# lorelei_A_v1.net
KiCad netlist of a schematic drawn in EAGLE
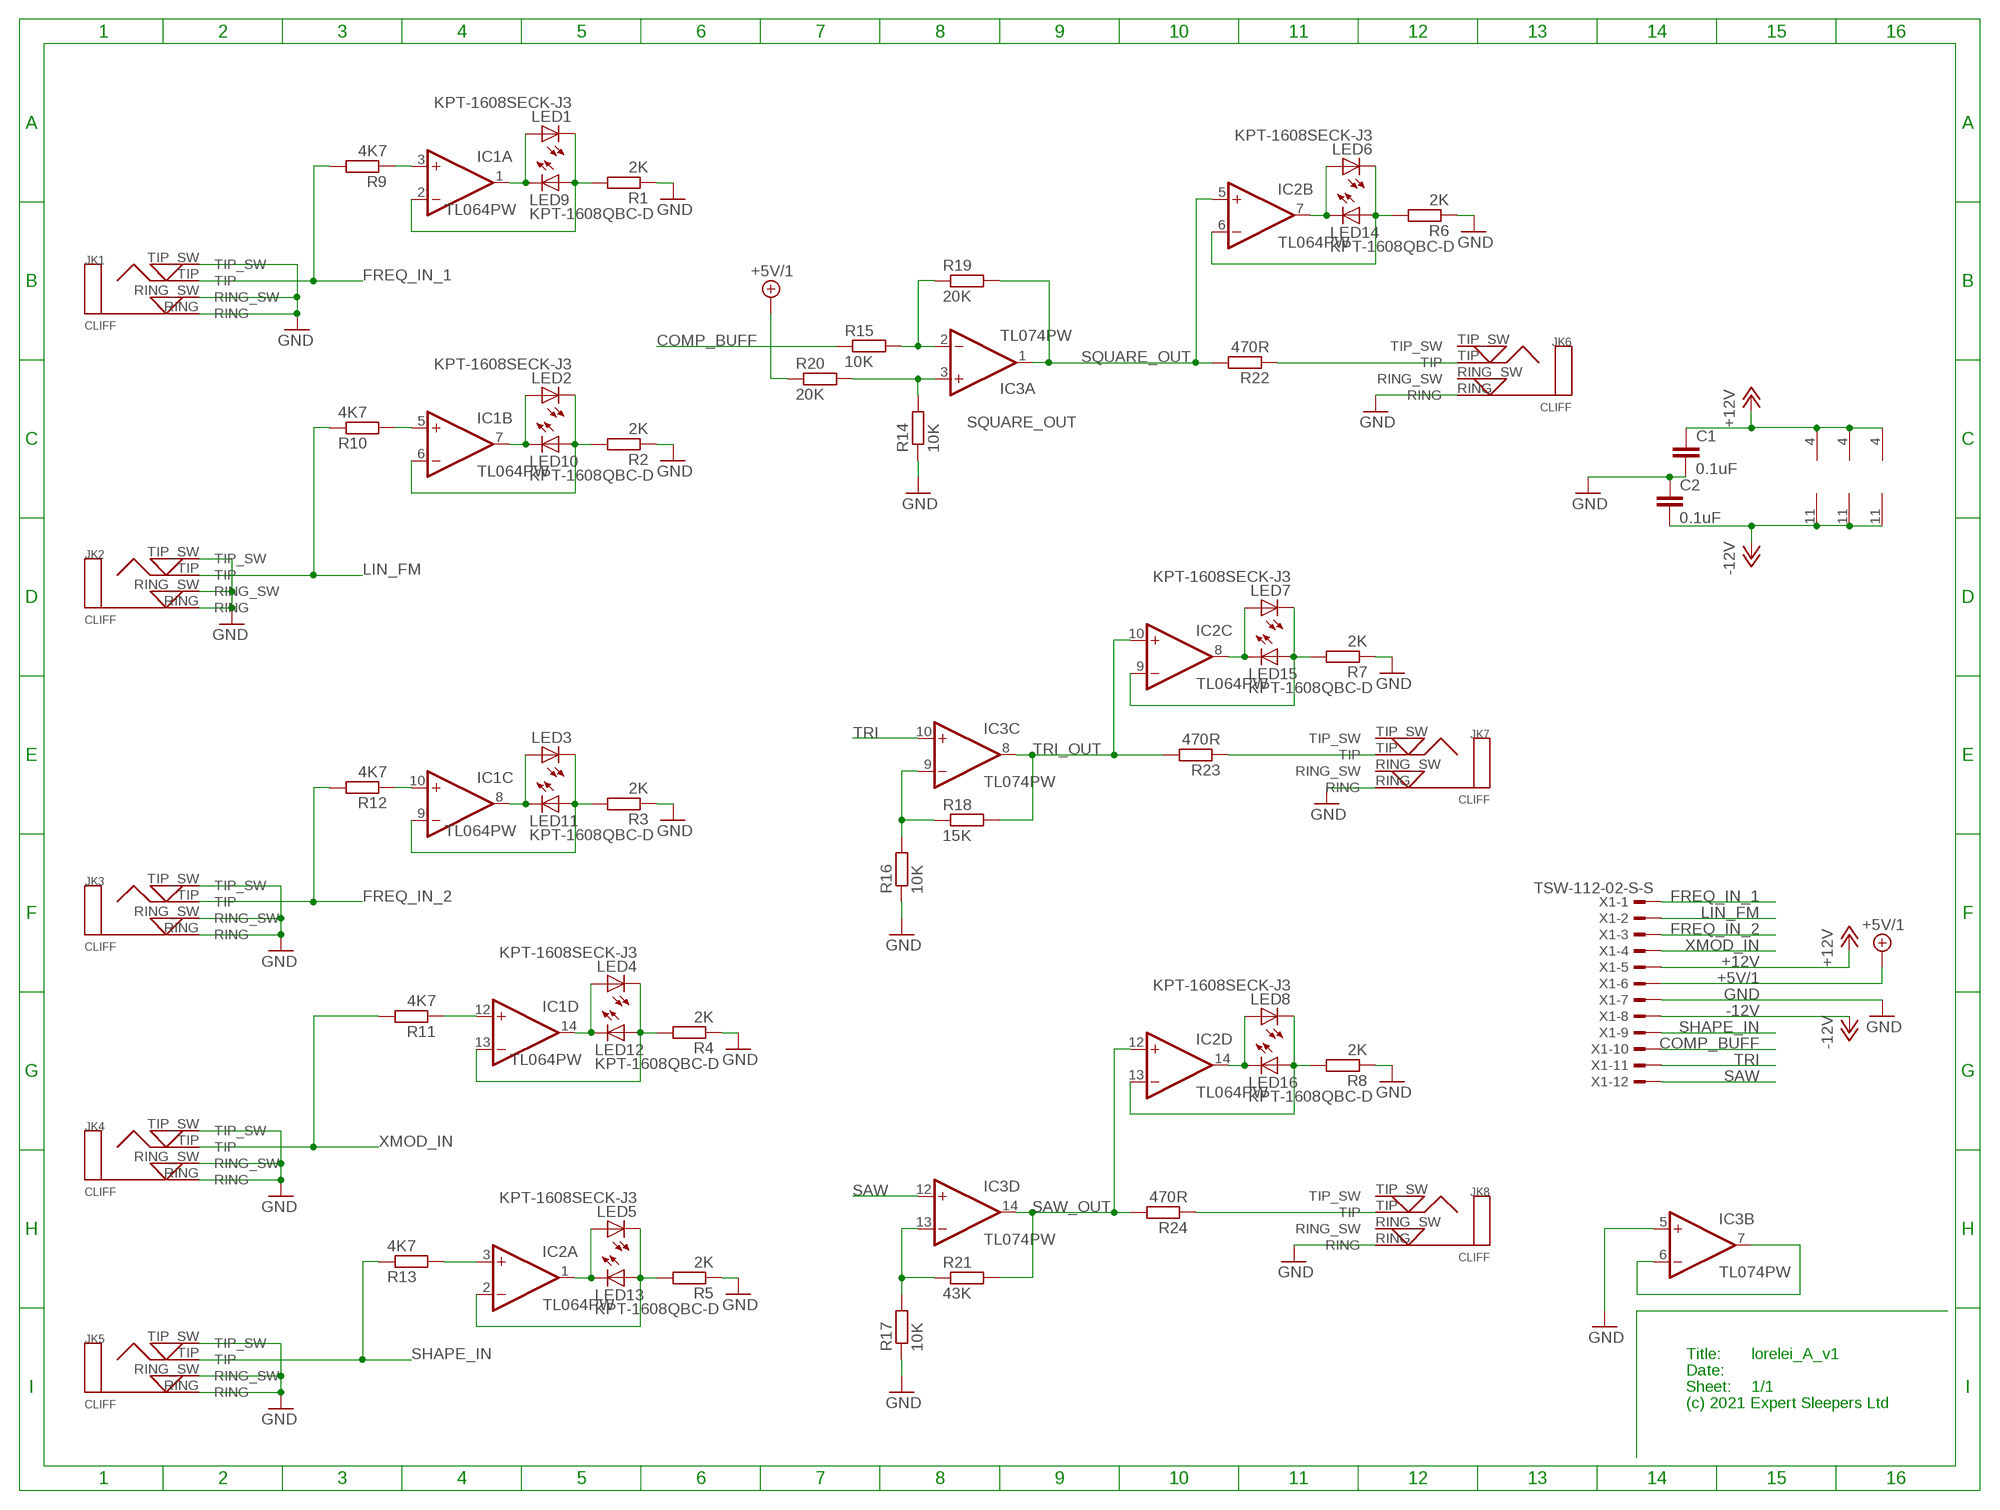
[diagram p0: schematic, sheet 1]

(export (version "E")
  (design (tool "Eeschema 10.0.6"))
  (components
    (comp (ref "C1")
      (value "0.1uF")
      (footprint "eagle-import:C0402")
      (libsource (lib "eagle-import") (part "C-EUC0402"))
    )
    (comp (ref "C2")
      (value "0.1uF")
      (footprint "eagle-import:C0402")
      (libsource (lib "eagle-import") (part "C-EUC0402"))
    )
    (comp (ref "IC1")
      (value "TL064PW")
      (footprint "eagle-import:PW_R-PDSO-G14")
      (libsource (lib "eagle-import") (part "TL074PW"))
    )
    (comp (ref "IC2")
      (value "TL064PW")
      (footprint "eagle-import:PW_R-PDSO-G14")
      (libsource (lib "eagle-import") (part "TL074PW"))
    )
    (comp (ref "IC3")
      (value "TL074PW")
      (footprint "eagle-import:PW_R-PDSO-G14")
      (libsource (lib "eagle-import") (part "TL074PW"))
    )
    (comp (ref "JK1")
      (value "CLIFF")
      (footprint "eagle-import:CLIFF3.5MMPCB")
      (libsource (lib "eagle-import") (part "CLIFF3.5MM_PCB_SW_JK"))
    )
    (comp (ref "JK2")
      (value "CLIFF")
      (footprint "eagle-import:CLIFF3.5MMPCB")
      (libsource (lib "eagle-import") (part "CLIFF3.5MM_PCB_SW_JK"))
    )
    (comp (ref "JK3")
      (value "CLIFF")
      (footprint "eagle-import:CLIFF3.5MMPCB")
      (libsource (lib "eagle-import") (part "CLIFF3.5MM_PCB_SW_JK"))
    )
    (comp (ref "JK4")
      (value "CLIFF")
      (footprint "eagle-import:CLIFF3.5MMPCB")
      (libsource (lib "eagle-import") (part "CLIFF3.5MM_PCB_SW_JK"))
    )
    (comp (ref "JK5")
      (value "CLIFF")
      (footprint "eagle-import:CLIFF3.5MMPCB")
      (libsource (lib "eagle-import") (part "CLIFF3.5MM_PCB_SW_JK"))
    )
    (comp (ref "JK6")
      (value "CLIFF")
      (footprint "eagle-import:CLIFF3.5MMPCB")
      (libsource (lib "eagle-import") (part "CLIFF3.5MM_PCB_SW_JK"))
    )
    (comp (ref "JK7")
      (value "CLIFF")
      (footprint "eagle-import:CLIFF3.5MMPCB")
      (libsource (lib "eagle-import") (part "CLIFF3.5MM_PCB_SW_JK"))
    )
    (comp (ref "JK8")
      (value "CLIFF")
      (footprint "eagle-import:CLIFF3.5MMPCB")
      (libsource (lib "eagle-import") (part "CLIFF3.5MM_PCB_SW_JK"))
    )
    (comp (ref "LED1")
      (value "KPT-1608SECK-J3")
      (footprint "eagle-import:CHIPLED_0603_LEFT")
      (libsource (lib "eagle-import") (part "KPT-1608SECK-J3"))
    )
    (comp (ref "LED2")
      (value "KPT-1608SECK-J3")
      (footprint "eagle-import:CHIPLED_0603_LEFT")
      (libsource (lib "eagle-import") (part "KPT-1608SECK-J3"))
    )
    (comp (ref "LED3")
      (value "KPT-1608SECK-J3")
      (footprint "eagle-import:CHIPLED_0603_LEFT")
      (libsource (lib "eagle-import") (part "KPT-1608SECK-J3"))
    )
    (comp (ref "LED4")
      (value "KPT-1608SECK-J3")
      (footprint "eagle-import:CHIPLED_0603_LEFT")
      (libsource (lib "eagle-import") (part "KPT-1608SECK-J3"))
    )
    (comp (ref "LED5")
      (value "KPT-1608SECK-J3")
      (footprint "eagle-import:CHIPLED_0603_LEFT")
      (libsource (lib "eagle-import") (part "KPT-1608SECK-J3"))
    )
    (comp (ref "LED6")
      (value "KPT-1608SECK-J3")
      (footprint "eagle-import:CHIPLED_0603_LEFT")
      (libsource (lib "eagle-import") (part "KPT-1608SECK-J3"))
    )
    (comp (ref "LED7")
      (value "KPT-1608SECK-J3")
      (footprint "eagle-import:CHIPLED_0603_LEFT")
      (libsource (lib "eagle-import") (part "KPT-1608SECK-J3"))
    )
    (comp (ref "LED8")
      (value "KPT-1608SECK-J3")
      (footprint "eagle-import:CHIPLED_0603_LEFT")
      (libsource (lib "eagle-import") (part "KPT-1608SECK-J3"))
    )
    (comp (ref "LED9")
      (value "KPT-1608QBC-D")
      (footprint "eagle-import:CHIPLED_0603_RIGHT")
      (libsource (lib "eagle-import") (part "KPT-1608QBC-D"))
    )
    (comp (ref "LED10")
      (value "KPT-1608QBC-D")
      (footprint "eagle-import:CHIPLED_0603_RIGHT")
      (libsource (lib "eagle-import") (part "KPT-1608QBC-D"))
    )
    (comp (ref "LED11")
      (value "KPT-1608QBC-D")
      (footprint "eagle-import:CHIPLED_0603_RIGHT")
      (libsource (lib "eagle-import") (part "KPT-1608QBC-D"))
    )
    (comp (ref "LED12")
      (value "KPT-1608QBC-D")
      (footprint "eagle-import:CHIPLED_0603_RIGHT")
      (libsource (lib "eagle-import") (part "KPT-1608QBC-D"))
    )
    (comp (ref "LED13")
      (value "KPT-1608QBC-D")
      (footprint "eagle-import:CHIPLED_0603_RIGHT")
      (libsource (lib "eagle-import") (part "KPT-1608QBC-D"))
    )
    (comp (ref "LED14")
      (value "KPT-1608QBC-D")
      (footprint "eagle-import:CHIPLED_0603_RIGHT")
      (libsource (lib "eagle-import") (part "KPT-1608QBC-D"))
    )
    (comp (ref "LED15")
      (value "KPT-1608QBC-D")
      (footprint "eagle-import:CHIPLED_0603_RIGHT")
      (libsource (lib "eagle-import") (part "KPT-1608QBC-D"))
    )
    (comp (ref "LED16")
      (value "KPT-1608QBC-D")
      (footprint "eagle-import:CHIPLED_0603_RIGHT")
      (libsource (lib "eagle-import") (part "KPT-1608QBC-D"))
    )
    (comp (ref "R1")
      (value "2K")
      (footprint "eagle-import:R1206")
      (libsource (lib "eagle-import") (part "R-EU_R1206"))
    )
    (comp (ref "R2")
      (value "2K")
      (footprint "eagle-import:R1206")
      (libsource (lib "eagle-import") (part "R-EU_R1206"))
    )
    (comp (ref "R3")
      (value "2K")
      (footprint "eagle-import:R1206")
      (libsource (lib "eagle-import") (part "R-EU_R1206"))
    )
    (comp (ref "R4")
      (value "2K")
      (footprint "eagle-import:R1206")
      (libsource (lib "eagle-import") (part "R-EU_R1206"))
    )
    (comp (ref "R5")
      (value "2K")
      (footprint "eagle-import:R1206")
      (libsource (lib "eagle-import") (part "R-EU_R1206"))
    )
    (comp (ref "R6")
      (value "2K")
      (footprint "eagle-import:R1206")
      (libsource (lib "eagle-import") (part "R-EU_R1206"))
    )
    (comp (ref "R7")
      (value "2K")
      (footprint "eagle-import:R1206")
      (libsource (lib "eagle-import") (part "R-EU_R1206"))
    )
    (comp (ref "R8")
      (value "2K")
      (footprint "eagle-import:R1206")
      (libsource (lib "eagle-import") (part "R-EU_R1206"))
    )
    (comp (ref "R9")
      (value "4K7")
      (footprint "eagle-import:R1206")
      (libsource (lib "eagle-import") (part "R-EU_R1206"))
    )
    (comp (ref "R10")
      (value "4K7")
      (footprint "eagle-import:R1206")
      (libsource (lib "eagle-import") (part "R-EU_R1206"))
    )
    (comp (ref "R11")
      (value "4K7")
      (footprint "eagle-import:R1206")
      (libsource (lib "eagle-import") (part "R-EU_R1206"))
    )
    (comp (ref "R12")
      (value "4K7")
      (footprint "eagle-import:R1206")
      (libsource (lib "eagle-import") (part "R-EU_R1206"))
    )
    (comp (ref "R13")
      (value "4K7")
      (footprint "eagle-import:R1206")
      (libsource (lib "eagle-import") (part "R-EU_R1206"))
    )
    (comp (ref "R14")
      (value "10K")
      (footprint "eagle-import:R0603")
      (libsource (lib "eagle-import") (part "R-EU_R0603"))
    )
    (comp (ref "R15")
      (value "10K")
      (footprint "eagle-import:R0603")
      (libsource (lib "eagle-import") (part "R-EU_R0603"))
    )
    (comp (ref "R16")
      (value "10K")
      (footprint "eagle-import:R0603")
      (libsource (lib "eagle-import") (part "R-EU_R0603"))
    )
    (comp (ref "R17")
      (value "10K")
      (footprint "eagle-import:R0603")
      (libsource (lib "eagle-import") (part "R-EU_R0603"))
    )
    (comp (ref "R18")
      (value "15K")
      (footprint "eagle-import:R0603")
      (libsource (lib "eagle-import") (part "R-EU_R0603"))
    )
    (comp (ref "R19")
      (value "20K")
      (footprint "eagle-import:R0603")
      (libsource (lib "eagle-import") (part "R-EU_R0603"))
    )
    (comp (ref "R20")
      (value "20K")
      (footprint "eagle-import:R0603")
      (libsource (lib "eagle-import") (part "R-EU_R0603"))
    )
    (comp (ref "R21")
      (value "43K")
      (footprint "eagle-import:R0603")
      (libsource (lib "eagle-import") (part "R-EU_R0603"))
    )
    (comp (ref "R22")
      (value "470R")
      (footprint "eagle-import:R1206")
      (libsource (lib "eagle-import") (part "R-EU_R1206"))
    )
    (comp (ref "R23")
      (value "470R")
      (footprint "eagle-import:R1206")
      (libsource (lib "eagle-import") (part "R-EU_R1206"))
    )
    (comp (ref "R24")
      (value "470R")
      (footprint "eagle-import:R1206")
      (libsource (lib "eagle-import") (part "R-EU_R1206"))
    )
    (comp (ref "X1")
      (value "TSW-112-02-S-S")
      (footprint "eagle-import:TSW-112-02-S-S")
      (libsource (lib "eagle-import") (part "TSW-112-02-S-S"))
    )
  )
  (nets
    (net (code "1") (name "+5V{slash}1") (class "Default")
      (node (ref "R20") (pin "1") (pinfunction "1_1") (pintype "passive"))
      (node (ref "X1") (pin "6") (pinfunction "1_6") (pintype "passive"))
    )
    (net (code "2") (name "+12V") (class "Default")
      (node (ref "C1") (pin "1") (pinfunction "1_1") (pintype "passive"))
      (node (ref "IC1") (pin "4") (pinfunction "V+_4") (pintype "power_in"))
      (node (ref "IC2") (pin "4") (pinfunction "V+_4") (pintype "power_in"))
      (node (ref "IC3") (pin "4") (pinfunction "V+_4") (pintype "power_in"))
      (node (ref "X1") (pin "5") (pinfunction "1_5") (pintype "passive"))
    )
    (net (code "3") (name "-12V") (class "Default")
      (node (ref "C2") (pin "2") (pinfunction "2_2") (pintype "passive"))
      (node (ref "IC1") (pin "11") (pinfunction "V-_11") (pintype "power_in"))
      (node (ref "IC2") (pin "11") (pinfunction "V-_11") (pintype "power_in"))
      (node (ref "IC3") (pin "11") (pinfunction "V-_11") (pintype "power_in"))
      (node (ref "X1") (pin "8") (pinfunction "1_8") (pintype "passive"))
    )
    (net (code "4") (name "/COMP_BUFF") (class "Default")
      (node (ref "R15") (pin "1") (pinfunction "1_1") (pintype "passive"))
      (node (ref "X1") (pin "10") (pinfunction "1_10") (pintype "passive"))
    )
    (net (code "5") (name "/FREQ_IN_1") (class "Default")
      (node (ref "JK1") (pin "TIP") (pinfunction "TIP_TIP") (pintype "bidirectional"))
      (node (ref "R9") (pin "2") (pinfunction "2_2") (pintype "passive"))
      (node (ref "X1") (pin "1") (pinfunction "1_1") (pintype "passive"))
    )
    (net (code "6") (name "/FREQ_IN_2") (class "Default")
      (node (ref "JK3") (pin "TIP") (pinfunction "TIP_TIP") (pintype "bidirectional"))
      (node (ref "R12") (pin "2") (pinfunction "2_2") (pintype "passive"))
      (node (ref "X1") (pin "3") (pinfunction "1_3") (pintype "passive"))
    )
    (net (code "7") (name "/LIN_FM") (class "Default")
      (node (ref "JK2") (pin "TIP") (pinfunction "TIP_TIP") (pintype "bidirectional"))
      (node (ref "R10") (pin "1") (pinfunction "1_1") (pintype "passive"))
      (node (ref "X1") (pin "2") (pinfunction "1_2") (pintype "passive"))
    )
    (net (code "8") (name "/SAW") (class "Default")
      (node (ref "IC3") (pin "12") (pinfunction "+IN_12") (pintype "input"))
      (node (ref "X1") (pin "12") (pinfunction "1_12") (pintype "passive"))
    )
    (net (code "9") (name "/SAW_OUT") (class "Default")
      (node (ref "IC2") (pin "12") (pinfunction "+IN_12") (pintype "input"))
      (node (ref "IC3") (pin "14") (pinfunction "OUT_14") (pintype "output"))
      (node (ref "R21") (pin "2") (pinfunction "2_2") (pintype "passive"))
      (node (ref "R24") (pin "2") (pinfunction "2_2") (pintype "passive"))
    )
    (net (code "10") (name "/SHAPE_IN") (class "Default")
      (node (ref "JK5") (pin "TIP") (pinfunction "TIP_TIP") (pintype "bidirectional"))
      (node (ref "R13") (pin "1") (pinfunction "1_1") (pintype "passive"))
      (node (ref "X1") (pin "9") (pinfunction "1_9") (pintype "passive"))
    )
    (net (code "11") (name "/SQUARE_OUT") (class "Default")
      (node (ref "IC2") (pin "5") (pinfunction "+IN_5") (pintype "input"))
      (node (ref "IC3") (pin "1") (pinfunction "OUT_1") (pintype "output"))
      (node (ref "R19") (pin "2") (pinfunction "2_2") (pintype "passive"))
      (node (ref "R22") (pin "2") (pinfunction "2_2") (pintype "passive"))
    )
    (net (code "12") (name "/TRI") (class "Default")
      (node (ref "IC3") (pin "10") (pinfunction "+IN_10") (pintype "input"))
      (node (ref "X1") (pin "11") (pinfunction "1_11") (pintype "passive"))
    )
    (net (code "13") (name "/TRI_OUT") (class "Default")
      (node (ref "IC2") (pin "10") (pinfunction "+IN_10") (pintype "input"))
      (node (ref "IC3") (pin "8") (pinfunction "OUT_8") (pintype "output"))
      (node (ref "R18") (pin "2") (pinfunction "2_2") (pintype "passive"))
      (node (ref "R23") (pin "2") (pinfunction "2_2") (pintype "passive"))
    )
    (net (code "14") (name "/XMOD_IN") (class "Default")
      (node (ref "JK4") (pin "TIP") (pinfunction "TIP_TIP") (pintype "bidirectional"))
      (node (ref "R11") (pin "2") (pinfunction "2_2") (pintype "passive"))
      (node (ref "X1") (pin "4") (pinfunction "1_4") (pintype "passive"))
    )
    (net (code "15") (name "GND") (class "Default")
      (node (ref "C1") (pin "2") (pinfunction "2_2") (pintype "passive"))
      (node (ref "C2") (pin "1") (pinfunction "1_1") (pintype "passive"))
      (node (ref "IC3") (pin "5") (pinfunction "+IN_5") (pintype "input"))
      (node (ref "JK1") (pin "RING") (pinfunction "RING_RING") (pintype "bidirectional"))
      (node (ref "JK1") (pin "RING_SW") (pinfunction "RING_SW_RING_SW") (pintype "bidirectional"))
      (node (ref "JK1") (pin "TIP_SW") (pinfunction "TIP_SW_TIP_SW") (pintype "bidirectional"))
      (node (ref "JK2") (pin "RING") (pinfunction "RING_RING") (pintype "bidirectional"))
      (node (ref "JK2") (pin "RING_SW") (pinfunction "RING_SW_RING_SW") (pintype "bidirectional"))
      (node (ref "JK2") (pin "TIP_SW") (pinfunction "TIP_SW_TIP_SW") (pintype "bidirectional"))
      (node (ref "JK3") (pin "RING") (pinfunction "RING_RING") (pintype "bidirectional"))
      (node (ref "JK3") (pin "RING_SW") (pinfunction "RING_SW_RING_SW") (pintype "bidirectional"))
      (node (ref "JK3") (pin "TIP_SW") (pinfunction "TIP_SW_TIP_SW") (pintype "bidirectional"))
      (node (ref "JK4") (pin "RING") (pinfunction "RING_RING") (pintype "bidirectional"))
      (node (ref "JK4") (pin "RING_SW") (pinfunction "RING_SW_RING_SW") (pintype "bidirectional"))
      (node (ref "JK4") (pin "TIP_SW") (pinfunction "TIP_SW_TIP_SW") (pintype "bidirectional"))
      (node (ref "JK5") (pin "RING") (pinfunction "RING_RING") (pintype "bidirectional"))
      (node (ref "JK5") (pin "RING_SW") (pinfunction "RING_SW_RING_SW") (pintype "bidirectional"))
      (node (ref "JK5") (pin "TIP_SW") (pinfunction "TIP_SW_TIP_SW") (pintype "bidirectional"))
      (node (ref "JK6") (pin "RING") (pinfunction "RING_RING") (pintype "bidirectional"))
      (node (ref "JK7") (pin "RING") (pinfunction "RING_RING") (pintype "bidirectional"))
      (node (ref "JK8") (pin "RING") (pinfunction "RING_RING") (pintype "bidirectional"))
      (node (ref "R1") (pin "1") (pinfunction "1_1") (pintype "passive"))
      (node (ref "R14") (pin "1") (pinfunction "1_1") (pintype "passive"))
      (node (ref "R16") (pin "1") (pinfunction "1_1") (pintype "passive"))
      (node (ref "R17") (pin "1") (pinfunction "1_1") (pintype "passive"))
      (node (ref "R2") (pin "1") (pinfunction "1_1") (pintype "passive"))
      (node (ref "R3") (pin "1") (pinfunction "1_1") (pintype "passive"))
      (node (ref "R4") (pin "1") (pinfunction "1_1") (pintype "passive"))
      (node (ref "R5") (pin "1") (pinfunction "1_1") (pintype "passive"))
      (node (ref "R6") (pin "1") (pinfunction "1_1") (pintype "passive"))
      (node (ref "R7") (pin "1") (pinfunction "1_1") (pintype "passive"))
      (node (ref "R8") (pin "1") (pinfunction "1_1") (pintype "passive"))
      (node (ref "X1") (pin "7") (pinfunction "1_7") (pintype "passive"))
    )
    (net (code "16") (name "Net-(IC1A-+IN)") (class "Default")
      (node (ref "IC1") (pin "3") (pinfunction "+IN_3") (pintype "input"))
      (node (ref "R9") (pin "1") (pinfunction "1_1") (pintype "passive"))
    )
    (net (code "17") (name "Net-(IC1A--IN)") (class "Default")
      (node (ref "IC1") (pin "2") (pinfunction "-IN_2") (pintype "input"))
      (node (ref "LED1") (pin "1") (pinfunction "C_1") (pintype "passive"))
      (node (ref "LED9") (pin "1") (pinfunction "A_1") (pintype "passive"))
      (node (ref "R1") (pin "2") (pinfunction "2_2") (pintype "passive"))
    )
    (net (code "18") (name "Net-(IC1A-OUT)") (class "Default")
      (node (ref "IC1") (pin "1") (pinfunction "OUT_1") (pintype "output"))
      (node (ref "LED1") (pin "2") (pinfunction "A_2") (pintype "passive"))
      (node (ref "LED9") (pin "2") (pinfunction "C_2") (pintype "passive"))
    )
    (net (code "19") (name "Net-(IC1B-+IN)") (class "Default")
      (node (ref "IC1") (pin "5") (pinfunction "+IN_5") (pintype "input"))
      (node (ref "R10") (pin "2") (pinfunction "2_2") (pintype "passive"))
    )
    (net (code "20") (name "Net-(IC1B--IN)") (class "Default")
      (node (ref "IC1") (pin "6") (pinfunction "-IN_6") (pintype "input"))
      (node (ref "LED10") (pin "1") (pinfunction "A_1") (pintype "passive"))
      (node (ref "LED2") (pin "1") (pinfunction "C_1") (pintype "passive"))
      (node (ref "R2") (pin "2") (pinfunction "2_2") (pintype "passive"))
    )
    (net (code "21") (name "Net-(IC1B-OUT)") (class "Default")
      (node (ref "IC1") (pin "7") (pinfunction "OUT_7") (pintype "output"))
      (node (ref "LED10") (pin "2") (pinfunction "C_2") (pintype "passive"))
      (node (ref "LED2") (pin "2") (pinfunction "A_2") (pintype "passive"))
    )
    (net (code "22") (name "Net-(IC1C-+IN)") (class "Default")
      (node (ref "IC1") (pin "10") (pinfunction "+IN_10") (pintype "input"))
      (node (ref "R12") (pin "1") (pinfunction "1_1") (pintype "passive"))
    )
    (net (code "23") (name "Net-(IC1C--IN)") (class "Default")
      (node (ref "IC1") (pin "9") (pinfunction "-IN_9") (pintype "input"))
      (node (ref "LED11") (pin "1") (pinfunction "A_1") (pintype "passive"))
      (node (ref "LED3") (pin "1") (pinfunction "C_1") (pintype "passive"))
      (node (ref "R3") (pin "2") (pinfunction "2_2") (pintype "passive"))
    )
    (net (code "24") (name "Net-(IC1C-OUT)") (class "Default")
      (node (ref "IC1") (pin "8") (pinfunction "OUT_8") (pintype "output"))
      (node (ref "LED11") (pin "2") (pinfunction "C_2") (pintype "passive"))
      (node (ref "LED3") (pin "2") (pinfunction "A_2") (pintype "passive"))
    )
    (net (code "25") (name "Net-(IC1D-+IN)") (class "Default")
      (node (ref "IC1") (pin "12") (pinfunction "+IN_12") (pintype "input"))
      (node (ref "R11") (pin "1") (pinfunction "1_1") (pintype "passive"))
    )
    (net (code "26") (name "Net-(IC1D--IN)") (class "Default")
      (node (ref "IC1") (pin "13") (pinfunction "-IN_13") (pintype "input"))
      (node (ref "LED12") (pin "1") (pinfunction "A_1") (pintype "passive"))
      (node (ref "LED4") (pin "1") (pinfunction "C_1") (pintype "passive"))
      (node (ref "R4") (pin "2") (pinfunction "2_2") (pintype "passive"))
    )
    (net (code "27") (name "Net-(IC1D-OUT)") (class "Default")
      (node (ref "IC1") (pin "14") (pinfunction "OUT_14") (pintype "output"))
      (node (ref "LED12") (pin "2") (pinfunction "C_2") (pintype "passive"))
      (node (ref "LED4") (pin "2") (pinfunction "A_2") (pintype "passive"))
    )
    (net (code "28") (name "Net-(IC2A-+IN)") (class "Default")
      (node (ref "IC2") (pin "3") (pinfunction "+IN_3") (pintype "input"))
      (node (ref "R13") (pin "2") (pinfunction "2_2") (pintype "passive"))
    )
    (net (code "29") (name "Net-(IC2A--IN)") (class "Default")
      (node (ref "IC2") (pin "2") (pinfunction "-IN_2") (pintype "input"))
      (node (ref "LED13") (pin "1") (pinfunction "A_1") (pintype "passive"))
      (node (ref "LED5") (pin "1") (pinfunction "C_1") (pintype "passive"))
      (node (ref "R5") (pin "2") (pinfunction "2_2") (pintype "passive"))
    )
    (net (code "30") (name "Net-(IC2A-OUT)") (class "Default")
      (node (ref "IC2") (pin "1") (pinfunction "OUT_1") (pintype "output"))
      (node (ref "LED13") (pin "2") (pinfunction "C_2") (pintype "passive"))
      (node (ref "LED5") (pin "2") (pinfunction "A_2") (pintype "passive"))
    )
    (net (code "31") (name "Net-(IC2B--IN)") (class "Default")
      (node (ref "IC2") (pin "6") (pinfunction "-IN_6") (pintype "input"))
      (node (ref "LED14") (pin "1") (pinfunction "A_1") (pintype "passive"))
      (node (ref "LED6") (pin "1") (pinfunction "C_1") (pintype "passive"))
      (node (ref "R6") (pin "2") (pinfunction "2_2") (pintype "passive"))
    )
    (net (code "32") (name "Net-(IC2B-OUT)") (class "Default")
      (node (ref "IC2") (pin "7") (pinfunction "OUT_7") (pintype "output"))
      (node (ref "LED14") (pin "2") (pinfunction "C_2") (pintype "passive"))
      (node (ref "LED6") (pin "2") (pinfunction "A_2") (pintype "passive"))
    )
    (net (code "33") (name "Net-(IC2C--IN)") (class "Default")
      (node (ref "IC2") (pin "9") (pinfunction "-IN_9") (pintype "input"))
      (node (ref "LED15") (pin "1") (pinfunction "A_1") (pintype "passive"))
      (node (ref "LED7") (pin "1") (pinfunction "C_1") (pintype "passive"))
      (node (ref "R7") (pin "2") (pinfunction "2_2") (pintype "passive"))
    )
    (net (code "34") (name "Net-(IC2C-OUT)") (class "Default")
      (node (ref "IC2") (pin "8") (pinfunction "OUT_8") (pintype "output"))
      (node (ref "LED15") (pin "2") (pinfunction "C_2") (pintype "passive"))
      (node (ref "LED7") (pin "2") (pinfunction "A_2") (pintype "passive"))
    )
    (net (code "35") (name "Net-(IC2D--IN)") (class "Default")
      (node (ref "IC2") (pin "13") (pinfunction "-IN_13") (pintype "input"))
      (node (ref "LED16") (pin "1") (pinfunction "A_1") (pintype "passive"))
      (node (ref "LED8") (pin "1") (pinfunction "C_1") (pintype "passive"))
      (node (ref "R8") (pin "2") (pinfunction "2_2") (pintype "passive"))
    )
    (net (code "36") (name "Net-(IC2D-OUT)") (class "Default")
      (node (ref "IC2") (pin "14") (pinfunction "OUT_14") (pintype "output"))
      (node (ref "LED16") (pin "2") (pinfunction "C_2") (pintype "passive"))
      (node (ref "LED8") (pin "2") (pinfunction "A_2") (pintype "passive"))
    )
    (net (code "37") (name "Net-(IC3A-+IN)") (class "Default")
      (node (ref "IC3") (pin "3") (pinfunction "+IN_3") (pintype "input"))
      (node (ref "R14") (pin "2") (pinfunction "2_2") (pintype "passive"))
      (node (ref "R20") (pin "2") (pinfunction "2_2") (pintype "passive"))
    )
    (net (code "38") (name "Net-(IC3A--IN)") (class "Default")
      (node (ref "IC3") (pin "2") (pinfunction "-IN_2") (pintype "input"))
      (node (ref "R15") (pin "2") (pinfunction "2_2") (pintype "passive"))
      (node (ref "R19") (pin "1") (pinfunction "1_1") (pintype "passive"))
    )
    (net (code "39") (name "Net-(IC3B--IN)") (class "Default")
      (node (ref "IC3") (pin "6") (pinfunction "-IN_6") (pintype "input"))
      (node (ref "IC3") (pin "7") (pinfunction "OUT_7") (pintype "output"))
    )
    (net (code "40") (name "Net-(IC3C--IN)") (class "Default")
      (node (ref "IC3") (pin "9") (pinfunction "-IN_9") (pintype "input"))
      (node (ref "R16") (pin "2") (pinfunction "2_2") (pintype "passive"))
      (node (ref "R18") (pin "1") (pinfunction "1_1") (pintype "passive"))
    )
    (net (code "41") (name "Net-(IC3D--IN)") (class "Default")
      (node (ref "IC3") (pin "13") (pinfunction "-IN_13") (pintype "input"))
      (node (ref "R17") (pin "2") (pinfunction "2_2") (pintype "passive"))
      (node (ref "R21") (pin "1") (pinfunction "1_1") (pintype "passive"))
    )
    (net (code "42") (name "Net-(JK6-PadTIP)") (class "Default")
      (node (ref "JK6") (pin "TIP") (pinfunction "TIP_TIP") (pintype "bidirectional"))
      (node (ref "R22") (pin "1") (pinfunction "1_1") (pintype "passive"))
    )
    (net (code "43") (name "Net-(JK7-PadTIP)") (class "Default")
      (node (ref "JK7") (pin "TIP") (pinfunction "TIP_TIP") (pintype "bidirectional"))
      (node (ref "R23") (pin "1") (pinfunction "1_1") (pintype "passive"))
    )
    (net (code "44") (name "Net-(JK8-PadTIP)") (class "Default")
      (node (ref "JK8") (pin "TIP") (pinfunction "TIP_TIP") (pintype "bidirectional"))
      (node (ref "R24") (pin "1") (pinfunction "1_1") (pintype "passive"))
    )
    (net (code "45") (name "unconnected-(JK6-PadRING_SW)") (class "Default")
      (node (ref "JK6") (pin "RING_SW") (pinfunction "RING_SW_RING_SW") (pintype "bidirectional"))
    )
    (net (code "46") (name "unconnected-(JK6-PadTIP_SW)") (class "Default")
      (node (ref "JK6") (pin "TIP_SW") (pinfunction "TIP_SW_TIP_SW") (pintype "bidirectional"))
    )
    (net (code "47") (name "unconnected-(JK7-PadRING_SW)") (class "Default")
      (node (ref "JK7") (pin "RING_SW") (pinfunction "RING_SW_RING_SW") (pintype "bidirectional"))
    )
    (net (code "48") (name "unconnected-(JK7-PadTIP_SW)") (class "Default")
      (node (ref "JK7") (pin "TIP_SW") (pinfunction "TIP_SW_TIP_SW") (pintype "bidirectional"))
    )
    (net (code "49") (name "unconnected-(JK8-PadRING_SW)") (class "Default")
      (node (ref "JK8") (pin "RING_SW") (pinfunction "RING_SW_RING_SW") (pintype "bidirectional"))
    )
    (net (code "50") (name "unconnected-(JK8-PadTIP_SW)") (class "Default")
      (node (ref "JK8") (pin "TIP_SW") (pinfunction "TIP_SW_TIP_SW") (pintype "bidirectional"))
    )
  )
)
